# arduinoModuleSVS.net
KiCad netlist of a schematic drawn in EAGLE
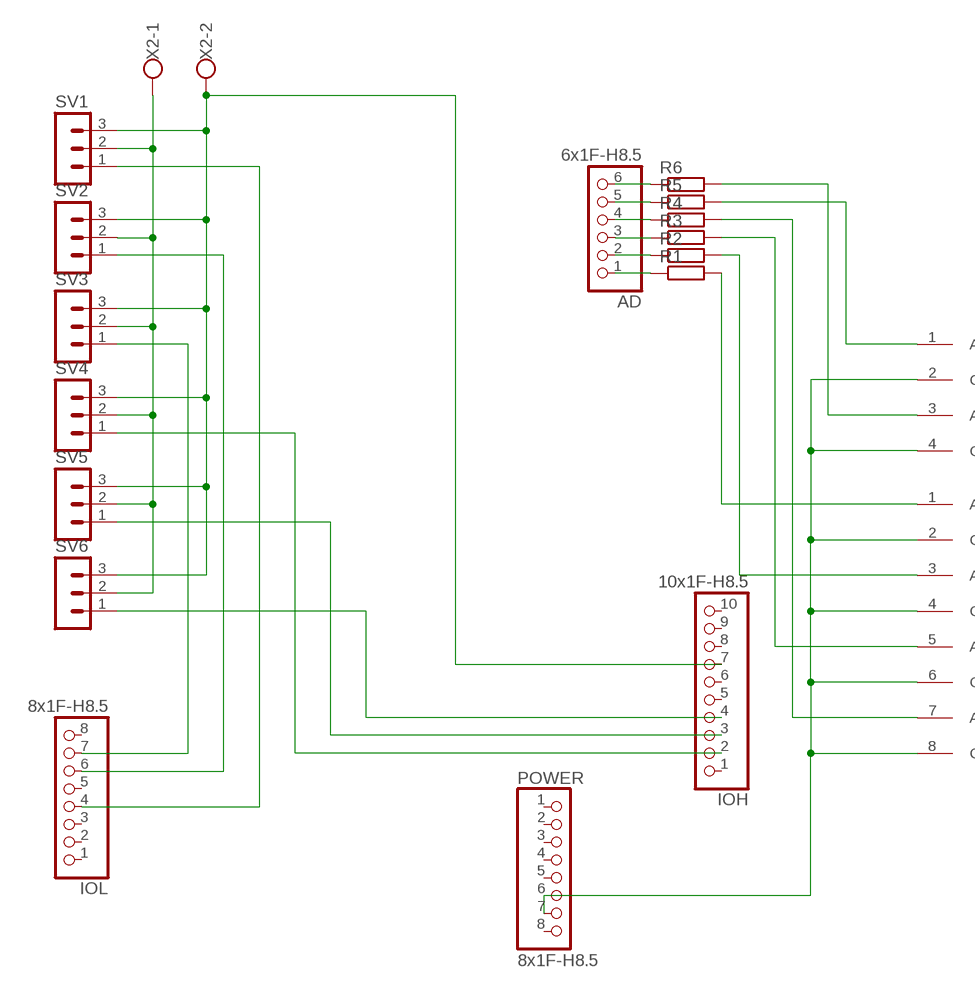
[diagram p0: schematic, sheet 1, part 1 of 2]
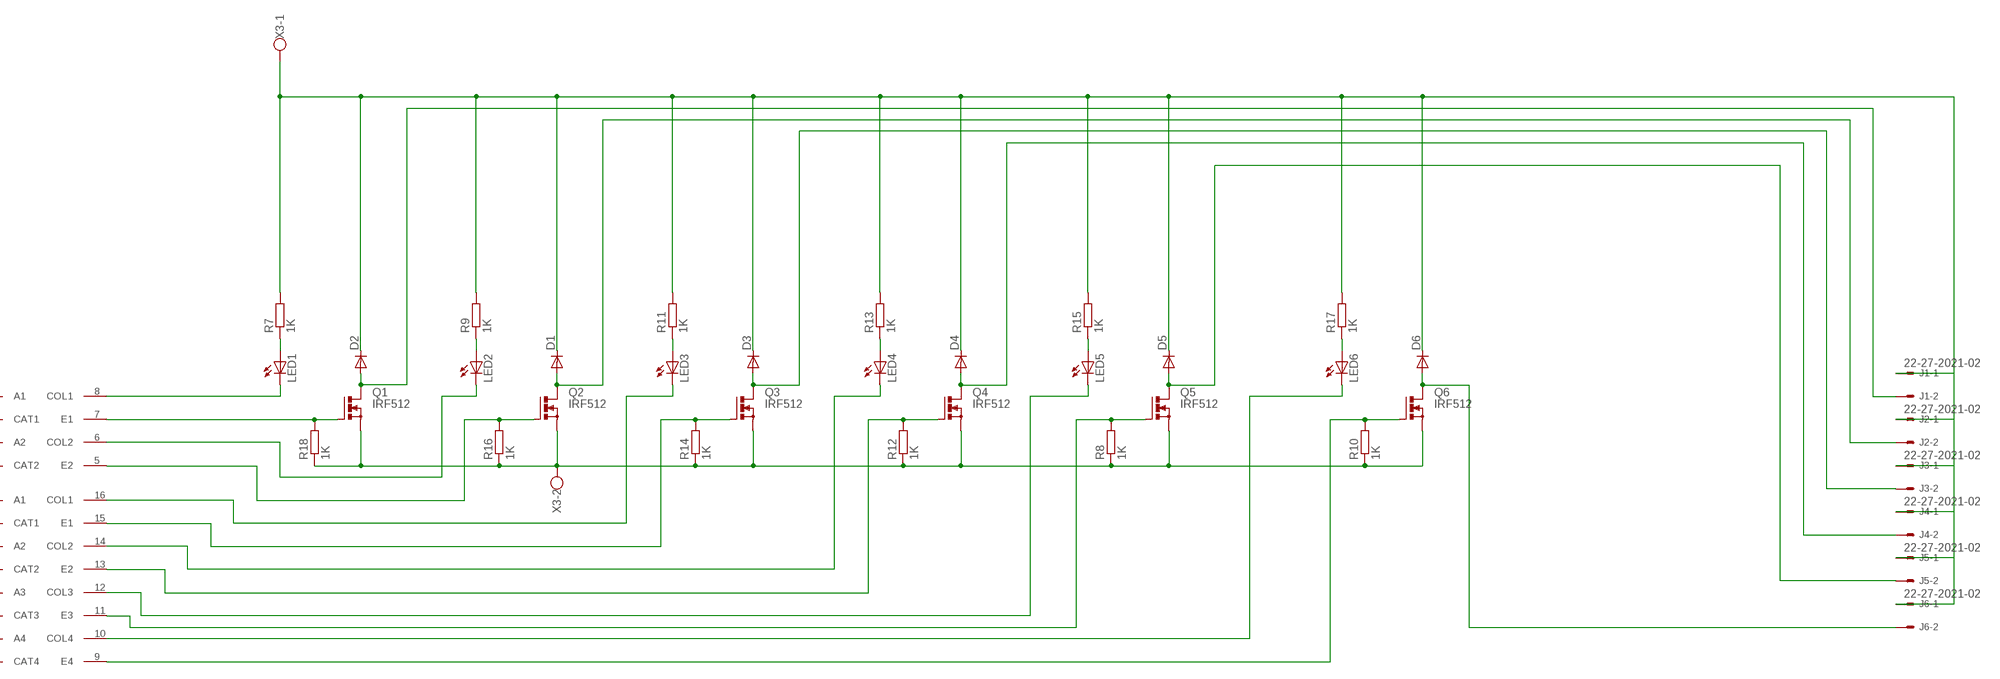
[diagram p1: schematic, sheet 1, part 2 of 2]

(export (version "E")
  (design (tool "Eeschema 10.0.6"))
  (components
    (comp (ref "AD")
      (value "6x1F-H8.5")
      (footprint "eagle-import:SMARTPRJ_1X06")
      (libsource (lib "eagle-import") (part "SMARTPRJ_PINHD-1X6"))
    )
    (comp (ref "D1")
      (value "DIODE-SOD123")
      (footprint "eagle-import:SOD123")
      (libsource (lib "eagle-import") (part "DIODE-SOD123"))
    )
    (comp (ref "D2")
      (value "DIODE-SOD123")
      (footprint "eagle-import:SOD123")
      (libsource (lib "eagle-import") (part "DIODE-SOD123"))
    )
    (comp (ref "D3")
      (value "DIODE-SOD123")
      (footprint "eagle-import:SOD123")
      (libsource (lib "eagle-import") (part "DIODE-SOD123"))
    )
    (comp (ref "D4")
      (value "DIODE-SOD123")
      (footprint "eagle-import:SOD123")
      (libsource (lib "eagle-import") (part "DIODE-SOD123"))
    )
    (comp (ref "D5")
      (value "DIODE-SOD123")
      (footprint "eagle-import:SOD123")
      (libsource (lib "eagle-import") (part "DIODE-SOD123"))
    )
    (comp (ref "D6")
      (value "DIODE-SOD123")
      (footprint "eagle-import:SOD123")
      (libsource (lib "eagle-import") (part "DIODE-SOD123"))
    )
    (comp (ref "IOH")
      (value "10x1F-H8.5")
      (footprint "eagle-import:SMARTPRJ_1X10")
      (libsource (lib "eagle-import") (part "SMARTPRJ_PINHD-1X10_ARD"))
    )
    (comp (ref "IOL")
      (value "8x1F-H8.5")
      (footprint "eagle-import:SMARTPRJ_1X08")
      (libsource (lib "eagle-import") (part "SMARTPRJ_PINHD-1X8"))
    )
    (comp (ref "J1")
      (value "22-27-2021-02")
      (footprint "eagle-import:6410-02")
      (libsource (lib "eagle-import") (part "22-?-0227-2021"))
    )
    (comp (ref "J2")
      (value "22-27-2021-02")
      (footprint "eagle-import:6410-02")
      (libsource (lib "eagle-import") (part "22-?-0227-2021"))
    )
    (comp (ref "J3")
      (value "22-27-2021-02")
      (footprint "eagle-import:6410-02")
      (libsource (lib "eagle-import") (part "22-?-0227-2021"))
    )
    (comp (ref "J4")
      (value "22-27-2021-02")
      (footprint "eagle-import:6410-02")
      (libsource (lib "eagle-import") (part "22-?-0227-2021"))
    )
    (comp (ref "J5")
      (value "22-27-2021-02")
      (footprint "eagle-import:6410-02")
      (libsource (lib "eagle-import") (part "22-?-0227-2021"))
    )
    (comp (ref "J6")
      (value "22-27-2021-02")
      (footprint "eagle-import:6410-02")
      (libsource (lib "eagle-import") (part "22-?-0227-2021"))
    )
    (comp (ref "LED1")
      (value "LED3MM")
      (footprint "eagle-import:LED3MM")
      (libsource (lib "eagle-import") (part "LED3MM"))
    )
    (comp (ref "LED2")
      (value "LED3MM")
      (footprint "eagle-import:LED3MM")
      (libsource (lib "eagle-import") (part "LED3MM"))
    )
    (comp (ref "LED3")
      (value "LED3MM")
      (footprint "eagle-import:LED3MM")
      (libsource (lib "eagle-import") (part "LED3MM"))
    )
    (comp (ref "LED4")
      (value "LED3MM")
      (footprint "eagle-import:LED3MM")
      (libsource (lib "eagle-import") (part "LED3MM"))
    )
    (comp (ref "LED5")
      (value "LED3MM")
      (footprint "eagle-import:LED3MM")
      (libsource (lib "eagle-import") (part "LED3MM"))
    )
    (comp (ref "LED6")
      (value "LED3MM")
      (footprint "eagle-import:LED3MM")
      (libsource (lib "eagle-import") (part "LED3MM"))
    )
    (comp (ref "POWER")
      (value "8x1F-H8.5")
      (footprint "eagle-import:SMARTPRJ_1X08")
      (libsource (lib "eagle-import") (part "SMARTPRJ_PINHD-1X8"))
    )
    (comp (ref "Q1")
      (value "IRF512")
      (footprint "eagle-import:TO220BV")
      (libsource (lib "eagle-import") (part "IRF512"))
    )
    (comp (ref "Q2")
      (value "IRF512")
      (footprint "eagle-import:TO220BV")
      (libsource (lib "eagle-import") (part "IRF512"))
    )
    (comp (ref "Q3")
      (value "IRF512")
      (footprint "eagle-import:TO220BV")
      (libsource (lib "eagle-import") (part "IRF512"))
    )
    (comp (ref "Q4")
      (value "IRF512")
      (footprint "eagle-import:TO220BV")
      (libsource (lib "eagle-import") (part "IRF512"))
    )
    (comp (ref "Q5")
      (value "IRF512")
      (footprint "eagle-import:TO220BV")
      (libsource (lib "eagle-import") (part "IRF512"))
    )
    (comp (ref "Q6")
      (value "IRF512")
      (footprint "eagle-import:TO220BV")
      (libsource (lib "eagle-import") (part "IRF512"))
    )
    (comp (ref "R1")
      (value "R-EU_R0805")
      (footprint "eagle-import:R0805")
      (libsource (lib "eagle-import") (part "R-EU_R0805"))
    )
    (comp (ref "R2")
      (value "R-EU_R0805")
      (footprint "eagle-import:R0805")
      (libsource (lib "eagle-import") (part "R-EU_R0805"))
    )
    (comp (ref "R3")
      (value "R-EU_R0805")
      (footprint "eagle-import:R0805")
      (libsource (lib "eagle-import") (part "R-EU_R0805"))
    )
    (comp (ref "R4")
      (value "R-EU_R0805")
      (footprint "eagle-import:R0805")
      (libsource (lib "eagle-import") (part "R-EU_R0805"))
    )
    (comp (ref "R5")
      (value "R-EU_R0805")
      (footprint "eagle-import:R0805")
      (libsource (lib "eagle-import") (part "R-EU_R0805"))
    )
    (comp (ref "R6")
      (value "R-EU_R0805")
      (footprint "eagle-import:R0805")
      (libsource (lib "eagle-import") (part "R-EU_R0805"))
    )
    (comp (ref "R7")
      (value "1K")
      (footprint "eagle-import:R0805")
      (libsource (lib "eagle-import") (part "R-EU_R0805"))
    )
    (comp (ref "R8")
      (value "1K")
      (footprint "eagle-import:R0805")
      (libsource (lib "eagle-import") (part "R-EU_R0805"))
    )
    (comp (ref "R9")
      (value "1K")
      (footprint "eagle-import:R0805")
      (libsource (lib "eagle-import") (part "R-EU_R0805"))
    )
    (comp (ref "R10")
      (value "1K")
      (footprint "eagle-import:R0805")
      (libsource (lib "eagle-import") (part "R-EU_R0805"))
    )
    (comp (ref "R11")
      (value "1K")
      (footprint "eagle-import:R0805")
      (libsource (lib "eagle-import") (part "R-EU_R0805"))
    )
    (comp (ref "R12")
      (value "1K")
      (footprint "eagle-import:R0805")
      (libsource (lib "eagle-import") (part "R-EU_R0805"))
    )
    (comp (ref "R13")
      (value "1K")
      (footprint "eagle-import:R0805")
      (libsource (lib "eagle-import") (part "R-EU_R0805"))
    )
    (comp (ref "R14")
      (value "1K")
      (footprint "eagle-import:R0805")
      (libsource (lib "eagle-import") (part "R-EU_R0805"))
    )
    (comp (ref "R15")
      (value "1K")
      (footprint "eagle-import:R0805")
      (libsource (lib "eagle-import") (part "R-EU_R0805"))
    )
    (comp (ref "R16")
      (value "1K")
      (footprint "eagle-import:R0805")
      (libsource (lib "eagle-import") (part "R-EU_R0805"))
    )
    (comp (ref "R17")
      (value "1K")
      (footprint "eagle-import:R0805")
      (libsource (lib "eagle-import") (part "R-EU_R0805"))
    )
    (comp (ref "R18")
      (value "1K")
      (footprint "eagle-import:R0805")
      (libsource (lib "eagle-import") (part "R-EU_R0805"))
    )
    (comp (ref "SV1")
      (value "MA03-1")
      (footprint "eagle-import:MA03-1")
      (libsource (lib "eagle-import") (part "MA03-1"))
    )
    (comp (ref "SV2")
      (value "MA03-1")
      (footprint "eagle-import:MA03-1")
      (libsource (lib "eagle-import") (part "MA03-1"))
    )
    (comp (ref "SV3")
      (value "MA03-1")
      (footprint "eagle-import:MA03-1")
      (libsource (lib "eagle-import") (part "MA03-1"))
    )
    (comp (ref "SV4")
      (value "MA03-1")
      (footprint "eagle-import:MA03-1")
      (libsource (lib "eagle-import") (part "MA03-1"))
    )
    (comp (ref "SV5")
      (value "MA03-1")
      (footprint "eagle-import:MA03-1")
      (libsource (lib "eagle-import") (part "MA03-1"))
    )
    (comp (ref "SV6")
      (value "MA03-1")
      (footprint "eagle-import:MA03-1")
      (libsource (lib "eagle-import") (part "MA03-1"))
    )
    (comp (ref "U$1")
      (value "ACPL-847-W00E")
      (footprint "eagle-import:DIL16")
      (libsource (lib "eagle-import") (part "ACPL-847-W00E"))
    )
    (comp (ref "U$2")
      (value "ACPL-827-00CE")
      (footprint "eagle-import:DIL08")
      (libsource (lib "eagle-import") (part "ACPL-827-00CE"))
    )
    (comp (ref "X2")
      (value "W237-102")
      (footprint "eagle-import:W237-102")
      (fields (field (name "MPN") "237-102"))
      (libsource (lib "eagle-import") (part "W237-102"))
    )
    (comp (ref "X3")
      (value "W237-102")
      (footprint "eagle-import:W237-102")
      (fields (field (name "MPN") "237-102"))
      (libsource (lib "eagle-import") (part "W237-102"))
    )
  )
  (nets
    (net (code "1") (name "Net-(AD-Pad1)") (class "Default")
      (node (ref "AD") (pin "1") (pinfunction "1_1") (pintype "passive"))
      (node (ref "R1") (pin "1") (pinfunction "1_1") (pintype "passive"))
    )
    (net (code "2") (name "Net-(AD-Pad2)") (class "Default")
      (node (ref "AD") (pin "2") (pinfunction "2_2") (pintype "passive"))
      (node (ref "R2") (pin "1") (pinfunction "1_1") (pintype "passive"))
    )
    (net (code "3") (name "Net-(AD-Pad3)") (class "Default")
      (node (ref "AD") (pin "3") (pinfunction "3_3") (pintype "passive"))
      (node (ref "R3") (pin "1") (pinfunction "1_1") (pintype "passive"))
    )
    (net (code "4") (name "Net-(AD-Pad4)") (class "Default")
      (node (ref "AD") (pin "4") (pinfunction "4_4") (pintype "passive"))
      (node (ref "R4") (pin "1") (pinfunction "1_1") (pintype "passive"))
    )
    (net (code "5") (name "Net-(AD-Pad5)") (class "Default")
      (node (ref "AD") (pin "5") (pinfunction "5_5") (pintype "passive"))
      (node (ref "R5") (pin "1") (pinfunction "1_1") (pintype "passive"))
    )
    (net (code "6") (name "Net-(AD-Pad6)") (class "Default")
      (node (ref "AD") (pin "6") (pinfunction "6_6") (pintype "passive"))
      (node (ref "R6") (pin "1") (pinfunction "1_1") (pintype "passive"))
    )
    (net (code "7") (name "Net-(IOH-Pad2)") (class "Default")
      (node (ref "IOH") (pin "2") (pinfunction "2_2") (pintype "passive"))
      (node (ref "SV4") (pin "1") (pinfunction "1_1") (pintype "passive"))
    )
    (net (code "8") (name "Net-(IOH-Pad3)") (class "Default")
      (node (ref "IOH") (pin "3") (pinfunction "3_3") (pintype "passive"))
      (node (ref "SV5") (pin "1") (pinfunction "1_1") (pintype "passive"))
    )
    (net (code "9") (name "Net-(IOH-Pad4)") (class "Default")
      (node (ref "IOH") (pin "4") (pinfunction "4_4") (pintype "passive"))
      (node (ref "SV6") (pin "1") (pinfunction "1_1") (pintype "passive"))
    )
    (net (code "10") (name "Net-(IOL-Pad4)") (class "Default")
      (node (ref "IOL") (pin "4") (pinfunction "4_4") (pintype "passive"))
      (node (ref "SV1") (pin "1") (pinfunction "1_1") (pintype "passive"))
    )
    (net (code "11") (name "Net-(IOL-Pad6)") (class "Default")
      (node (ref "IOL") (pin "6") (pinfunction "6_6") (pintype "passive"))
      (node (ref "SV2") (pin "1") (pinfunction "1_1") (pintype "passive"))
    )
    (net (code "12") (name "Net-(IOL-Pad7)") (class "Default")
      (node (ref "IOL") (pin "7") (pinfunction "7_7") (pintype "passive"))
      (node (ref "SV3") (pin "1") (pinfunction "1_1") (pintype "passive"))
    )
    (net (code "13") (name "Net-(J1A-S)") (class "Default")
      (node (ref "D1") (pin "C") (pinfunction "C_C") (pintype "passive"))
      (node (ref "D2") (pin "C") (pinfunction "C_C") (pintype "passive"))
      (node (ref "D3") (pin "C") (pinfunction "C_C") (pintype "passive"))
      (node (ref "D4") (pin "C") (pinfunction "C_C") (pintype "passive"))
      (node (ref "D5") (pin "C") (pinfunction "C_C") (pintype "passive"))
      (node (ref "D6") (pin "C") (pinfunction "C_C") (pintype "passive"))
      (node (ref "J1") (pin "1") (pinfunction "S_1") (pintype "passive"))
      (node (ref "J2") (pin "1") (pinfunction "S_1") (pintype "passive"))
      (node (ref "J3") (pin "1") (pinfunction "S_1") (pintype "passive"))
      (node (ref "J4") (pin "1") (pinfunction "S_1") (pintype "passive"))
      (node (ref "J5") (pin "1") (pinfunction "S_1") (pintype "passive"))
      (node (ref "J6") (pin "1") (pinfunction "S_1") (pintype "passive"))
      (node (ref "R11") (pin "2") (pinfunction "2_2") (pintype "passive"))
      (node (ref "R13") (pin "2") (pinfunction "2_2") (pintype "passive"))
      (node (ref "R15") (pin "2") (pinfunction "2_2") (pintype "passive"))
      (node (ref "R17") (pin "2") (pinfunction "2_2") (pintype "passive"))
      (node (ref "R7") (pin "2") (pinfunction "2_2") (pintype "passive"))
      (node (ref "R9") (pin "2") (pinfunction "2_2") (pintype "passive"))
      (node (ref "X3") (pin "1") (pinfunction "KL_1") (pintype "passive"))
    )
    (net (code "14") (name "Net-(J1B-S)") (class "Default")
      (node (ref "D2") (pin "A") (pinfunction "A_A") (pintype "passive"))
      (node (ref "J1") (pin "2") (pinfunction "S_2") (pintype "passive"))
      (node (ref "Q1") (pin "D") (pinfunction "D_D") (pintype "passive"))
    )
    (net (code "15") (name "Net-(J2B-S)") (class "Default")
      (node (ref "D1") (pin "A") (pinfunction "A_A") (pintype "passive"))
      (node (ref "J2") (pin "2") (pinfunction "S_2") (pintype "passive"))
      (node (ref "Q2") (pin "D") (pinfunction "D_D") (pintype "passive"))
    )
    (net (code "16") (name "Net-(J3B-S)") (class "Default")
      (node (ref "D3") (pin "A") (pinfunction "A_A") (pintype "passive"))
      (node (ref "J3") (pin "2") (pinfunction "S_2") (pintype "passive"))
      (node (ref "Q3") (pin "D") (pinfunction "D_D") (pintype "passive"))
    )
    (net (code "17") (name "Net-(J4B-S)") (class "Default")
      (node (ref "D4") (pin "A") (pinfunction "A_A") (pintype "passive"))
      (node (ref "J4") (pin "2") (pinfunction "S_2") (pintype "passive"))
      (node (ref "Q4") (pin "D") (pinfunction "D_D") (pintype "passive"))
    )
    (net (code "18") (name "Net-(J5B-S)") (class "Default")
      (node (ref "D5") (pin "A") (pinfunction "A_A") (pintype "passive"))
      (node (ref "J5") (pin "2") (pinfunction "S_2") (pintype "passive"))
      (node (ref "Q5") (pin "D") (pinfunction "D_D") (pintype "passive"))
    )
    (net (code "19") (name "Net-(J6B-S)") (class "Default")
      (node (ref "D6") (pin "A") (pinfunction "A_A") (pintype "passive"))
      (node (ref "J6") (pin "2") (pinfunction "S_2") (pintype "passive"))
      (node (ref "Q6") (pin "D") (pinfunction "D_D") (pintype "passive"))
    )
    (net (code "20") (name "Net-(LED1-C)") (class "Default")
      (node (ref "LED1") (pin "K") (pinfunction "C_K") (pintype "passive"))
      (node (ref "U$2") (pin "8") (pinfunction "COL1_8") (pintype "bidirectional"))
    )
    (net (code "21") (name "Net-(LED1-PadA)") (class "Default")
      (node (ref "LED1") (pin "A") (pinfunction "A_A") (pintype "passive"))
      (node (ref "R7") (pin "1") (pinfunction "1_1") (pintype "passive"))
    )
    (net (code "22") (name "Net-(LED2-C)") (class "Default")
      (node (ref "LED2") (pin "K") (pinfunction "C_K") (pintype "passive"))
      (node (ref "U$2") (pin "6") (pinfunction "COL2_6") (pintype "bidirectional"))
    )
    (net (code "23") (name "Net-(LED2-PadA)") (class "Default")
      (node (ref "LED2") (pin "A") (pinfunction "A_A") (pintype "passive"))
      (node (ref "R9") (pin "1") (pinfunction "1_1") (pintype "passive"))
    )
    (net (code "24") (name "Net-(LED3-C)") (class "Default")
      (node (ref "LED3") (pin "K") (pinfunction "C_K") (pintype "passive"))
      (node (ref "U$1") (pin "16") (pinfunction "COL1_16") (pintype "bidirectional"))
    )
    (net (code "25") (name "Net-(LED3-PadA)") (class "Default")
      (node (ref "LED3") (pin "A") (pinfunction "A_A") (pintype "passive"))
      (node (ref "R11") (pin "1") (pinfunction "1_1") (pintype "passive"))
    )
    (net (code "26") (name "Net-(LED4-C)") (class "Default")
      (node (ref "LED4") (pin "K") (pinfunction "C_K") (pintype "passive"))
      (node (ref "U$1") (pin "14") (pinfunction "COL2_14") (pintype "bidirectional"))
    )
    (net (code "27") (name "Net-(LED4-PadA)") (class "Default")
      (node (ref "LED4") (pin "A") (pinfunction "A_A") (pintype "passive"))
      (node (ref "R13") (pin "1") (pinfunction "1_1") (pintype "passive"))
    )
    (net (code "28") (name "Net-(LED5-C)") (class "Default")
      (node (ref "LED5") (pin "K") (pinfunction "C_K") (pintype "passive"))
      (node (ref "U$1") (pin "12") (pinfunction "COL3_12") (pintype "bidirectional"))
    )
    (net (code "29") (name "Net-(LED5-PadA)") (class "Default")
      (node (ref "LED5") (pin "A") (pinfunction "A_A") (pintype "passive"))
      (node (ref "R15") (pin "1") (pinfunction "1_1") (pintype "passive"))
    )
    (net (code "30") (name "Net-(LED6-C)") (class "Default")
      (node (ref "LED6") (pin "K") (pinfunction "C_K") (pintype "passive"))
      (node (ref "U$1") (pin "10") (pinfunction "COL4_10") (pintype "bidirectional"))
    )
    (net (code "31") (name "Net-(LED6-PadA)") (class "Default")
      (node (ref "LED6") (pin "A") (pinfunction "A_A") (pintype "passive"))
      (node (ref "R17") (pin "1") (pinfunction "1_1") (pintype "passive"))
    )
    (net (code "32") (name "Net-(U$1-A1)") (class "Default")
      (node (ref "R1") (pin "2") (pinfunction "2_2") (pintype "passive"))
      (node (ref "U$1") (pin "1") (pinfunction "A1_1") (pintype "bidirectional"))
    )
    (net (code "33") (name "Net-(U$1-A2)") (class "Default")
      (node (ref "R2") (pin "2") (pinfunction "2_2") (pintype "passive"))
      (node (ref "U$1") (pin "3") (pinfunction "A2_3") (pintype "bidirectional"))
    )
    (net (code "34") (name "Net-(U$1-A3)") (class "Default")
      (node (ref "R3") (pin "2") (pinfunction "2_2") (pintype "passive"))
      (node (ref "U$1") (pin "5") (pinfunction "A3_5") (pintype "bidirectional"))
    )
    (net (code "35") (name "Net-(U$1-A4)") (class "Default")
      (node (ref "R4") (pin "2") (pinfunction "2_2") (pintype "passive"))
      (node (ref "U$1") (pin "7") (pinfunction "A4_7") (pintype "bidirectional"))
    )
    (net (code "36") (name "Net-(U$1-CAT1)") (class "Default")
      (node (ref "POWER") (pin "6") (pinfunction "6_6") (pintype "passive"))
      (node (ref "POWER") (pin "7") (pinfunction "7_7") (pintype "passive"))
      (node (ref "U$1") (pin "2") (pinfunction "CAT1_2") (pintype "bidirectional"))
      (node (ref "U$1") (pin "4") (pinfunction "CAT2_4") (pintype "bidirectional"))
      (node (ref "U$1") (pin "6") (pinfunction "CAT3_6") (pintype "bidirectional"))
      (node (ref "U$1") (pin "8") (pinfunction "CAT4_8") (pintype "bidirectional"))
      (node (ref "U$2") (pin "2") (pinfunction "CAT1_2") (pintype "bidirectional"))
      (node (ref "U$2") (pin "4") (pinfunction "CAT2_4") (pintype "bidirectional"))
    )
    (net (code "37") (name "Net-(U$1-E1)") (class "Default")
      (node (ref "Q3") (pin "G") (pinfunction "G_G") (pintype "passive"))
      (node (ref "R14") (pin "2") (pinfunction "2_2") (pintype "passive"))
      (node (ref "U$1") (pin "15") (pinfunction "E1_15") (pintype "bidirectional"))
    )
    (net (code "38") (name "Net-(U$1-E2)") (class "Default")
      (node (ref "Q4") (pin "G") (pinfunction "G_G") (pintype "passive"))
      (node (ref "R12") (pin "2") (pinfunction "2_2") (pintype "passive"))
      (node (ref "U$1") (pin "13") (pinfunction "E2_13") (pintype "bidirectional"))
    )
    (net (code "39") (name "Net-(U$1-E3)") (class "Default")
      (node (ref "Q5") (pin "G") (pinfunction "G_G") (pintype "passive"))
      (node (ref "R8") (pin "2") (pinfunction "2_2") (pintype "passive"))
      (node (ref "U$1") (pin "11") (pinfunction "E3_11") (pintype "bidirectional"))
    )
    (net (code "40") (name "Net-(U$1-E4)") (class "Default")
      (node (ref "Q6") (pin "G") (pinfunction "G_G") (pintype "passive"))
      (node (ref "R10") (pin "2") (pinfunction "2_2") (pintype "passive"))
      (node (ref "U$1") (pin "9") (pinfunction "E4_9") (pintype "bidirectional"))
    )
    (net (code "41") (name "Net-(U$2-A1)") (class "Default")
      (node (ref "R5") (pin "2") (pinfunction "2_2") (pintype "passive"))
      (node (ref "U$2") (pin "1") (pinfunction "A1_1") (pintype "bidirectional"))
    )
    (net (code "42") (name "Net-(U$2-A2)") (class "Default")
      (node (ref "R6") (pin "2") (pinfunction "2_2") (pintype "passive"))
      (node (ref "U$2") (pin "3") (pinfunction "A2_3") (pintype "bidirectional"))
    )
    (net (code "43") (name "Net-(U$2-E1)") (class "Default")
      (node (ref "Q1") (pin "G") (pinfunction "G_G") (pintype "passive"))
      (node (ref "R18") (pin "2") (pinfunction "2_2") (pintype "passive"))
      (node (ref "U$2") (pin "7") (pinfunction "E1_7") (pintype "bidirectional"))
    )
    (net (code "44") (name "Net-(U$2-E2)") (class "Default")
      (node (ref "Q2") (pin "G") (pinfunction "G_G") (pintype "passive"))
      (node (ref "R16") (pin "2") (pinfunction "2_2") (pintype "passive"))
      (node (ref "U$2") (pin "5") (pinfunction "E2_5") (pintype "bidirectional"))
    )
    (net (code "45") (name "Net-(X2A-KL)") (class "Default")
      (node (ref "SV1") (pin "2") (pinfunction "2_2") (pintype "passive"))
      (node (ref "SV2") (pin "2") (pinfunction "2_2") (pintype "passive"))
      (node (ref "SV3") (pin "2") (pinfunction "2_2") (pintype "passive"))
      (node (ref "SV4") (pin "2") (pinfunction "2_2") (pintype "passive"))
      (node (ref "SV5") (pin "2") (pinfunction "2_2") (pintype "passive"))
      (node (ref "SV6") (pin "2") (pinfunction "2_2") (pintype "passive"))
      (node (ref "X2") (pin "1") (pinfunction "KL_1") (pintype "passive"))
    )
    (net (code "46") (name "Net-(X2B-KL)") (class "Default")
      (node (ref "IOH") (pin "7") (pinfunction "7_7") (pintype "passive"))
      (node (ref "SV1") (pin "3") (pinfunction "3_3") (pintype "passive"))
      (node (ref "SV2") (pin "3") (pinfunction "3_3") (pintype "passive"))
      (node (ref "SV3") (pin "3") (pinfunction "3_3") (pintype "passive"))
      (node (ref "SV4") (pin "3") (pinfunction "3_3") (pintype "passive"))
      (node (ref "SV5") (pin "3") (pinfunction "3_3") (pintype "passive"))
      (node (ref "SV6") (pin "3") (pinfunction "3_3") (pintype "passive"))
      (node (ref "X2") (pin "2") (pinfunction "KL_2") (pintype "passive"))
    )
    (net (code "47") (name "Net-(X3B-KL)") (class "Default")
      (node (ref "Q1") (pin "S") (pinfunction "S_S") (pintype "passive"))
      (node (ref "Q2") (pin "S") (pinfunction "S_S") (pintype "passive"))
      (node (ref "Q3") (pin "S") (pinfunction "S_S") (pintype "passive"))
      (node (ref "Q4") (pin "S") (pinfunction "S_S") (pintype "passive"))
      (node (ref "Q5") (pin "S") (pinfunction "S_S") (pintype "passive"))
      (node (ref "Q6") (pin "S") (pinfunction "S_S") (pintype "passive"))
      (node (ref "R10") (pin "1") (pinfunction "1_1") (pintype "passive"))
      (node (ref "R12") (pin "1") (pinfunction "1_1") (pintype "passive"))
      (node (ref "R14") (pin "1") (pinfunction "1_1") (pintype "passive"))
      (node (ref "R16") (pin "1") (pinfunction "1_1") (pintype "passive"))
      (node (ref "R18") (pin "1") (pinfunction "1_1") (pintype "passive"))
      (node (ref "R8") (pin "1") (pinfunction "1_1") (pintype "passive"))
      (node (ref "X3") (pin "2") (pinfunction "KL_2") (pintype "passive"))
    )
    (net (code "48") (name "unconnected-(IOH-Pad1)") (class "Default")
      (node (ref "IOH") (pin "1") (pinfunction "1_1") (pintype "passive"))
    )
    (net (code "49") (name "unconnected-(IOH-Pad5)") (class "Default")
      (node (ref "IOH") (pin "5") (pinfunction "5_5") (pintype "passive"))
    )
    (net (code "50") (name "unconnected-(IOH-Pad6)") (class "Default")
      (node (ref "IOH") (pin "6") (pinfunction "6_6") (pintype "passive"))
    )
    (net (code "51") (name "unconnected-(IOH-Pad8)") (class "Default")
      (node (ref "IOH") (pin "8") (pinfunction "8_8") (pintype "passive"))
    )
    (net (code "52") (name "unconnected-(IOH-Pad9)") (class "Default")
      (node (ref "IOH") (pin "9") (pinfunction "9_9") (pintype "passive"))
    )
    (net (code "53") (name "unconnected-(IOH-Pad10)") (class "Default")
      (node (ref "IOH") (pin "10") (pinfunction "10_10") (pintype "passive"))
    )
    (net (code "54") (name "unconnected-(IOL-Pad1)") (class "Default")
      (node (ref "IOL") (pin "1") (pinfunction "1_1") (pintype "passive"))
    )
    (net (code "55") (name "unconnected-(IOL-Pad2)") (class "Default")
      (node (ref "IOL") (pin "2") (pinfunction "2_2") (pintype "passive"))
    )
    (net (code "56") (name "unconnected-(IOL-Pad3)") (class "Default")
      (node (ref "IOL") (pin "3") (pinfunction "3_3") (pintype "passive"))
    )
    (net (code "57") (name "unconnected-(IOL-Pad5)") (class "Default")
      (node (ref "IOL") (pin "5") (pinfunction "5_5") (pintype "passive"))
    )
    (net (code "58") (name "unconnected-(IOL-Pad8)") (class "Default")
      (node (ref "IOL") (pin "8") (pinfunction "8_8") (pintype "passive"))
    )
    (net (code "59") (name "unconnected-(POWER-Pad1)") (class "Default")
      (node (ref "POWER") (pin "1") (pinfunction "1_1") (pintype "passive"))
    )
    (net (code "60") (name "unconnected-(POWER-Pad2)") (class "Default")
      (node (ref "POWER") (pin "2") (pinfunction "2_2") (pintype "passive"))
    )
    (net (code "61") (name "unconnected-(POWER-Pad3)") (class "Default")
      (node (ref "POWER") (pin "3") (pinfunction "3_3") (pintype "passive"))
    )
    (net (code "62") (name "unconnected-(POWER-Pad4)") (class "Default")
      (node (ref "POWER") (pin "4") (pinfunction "4_4") (pintype "passive"))
    )
    (net (code "63") (name "unconnected-(POWER-Pad5)") (class "Default")
      (node (ref "POWER") (pin "5") (pinfunction "5_5") (pintype "passive"))
    )
    (net (code "64") (name "unconnected-(POWER-Pad8)") (class "Default")
      (node (ref "POWER") (pin "8") (pinfunction "8_8") (pintype "passive"))
    )
  )
)
